# breakout1.net
KiCad netlist of a schematic drawn in EAGLE
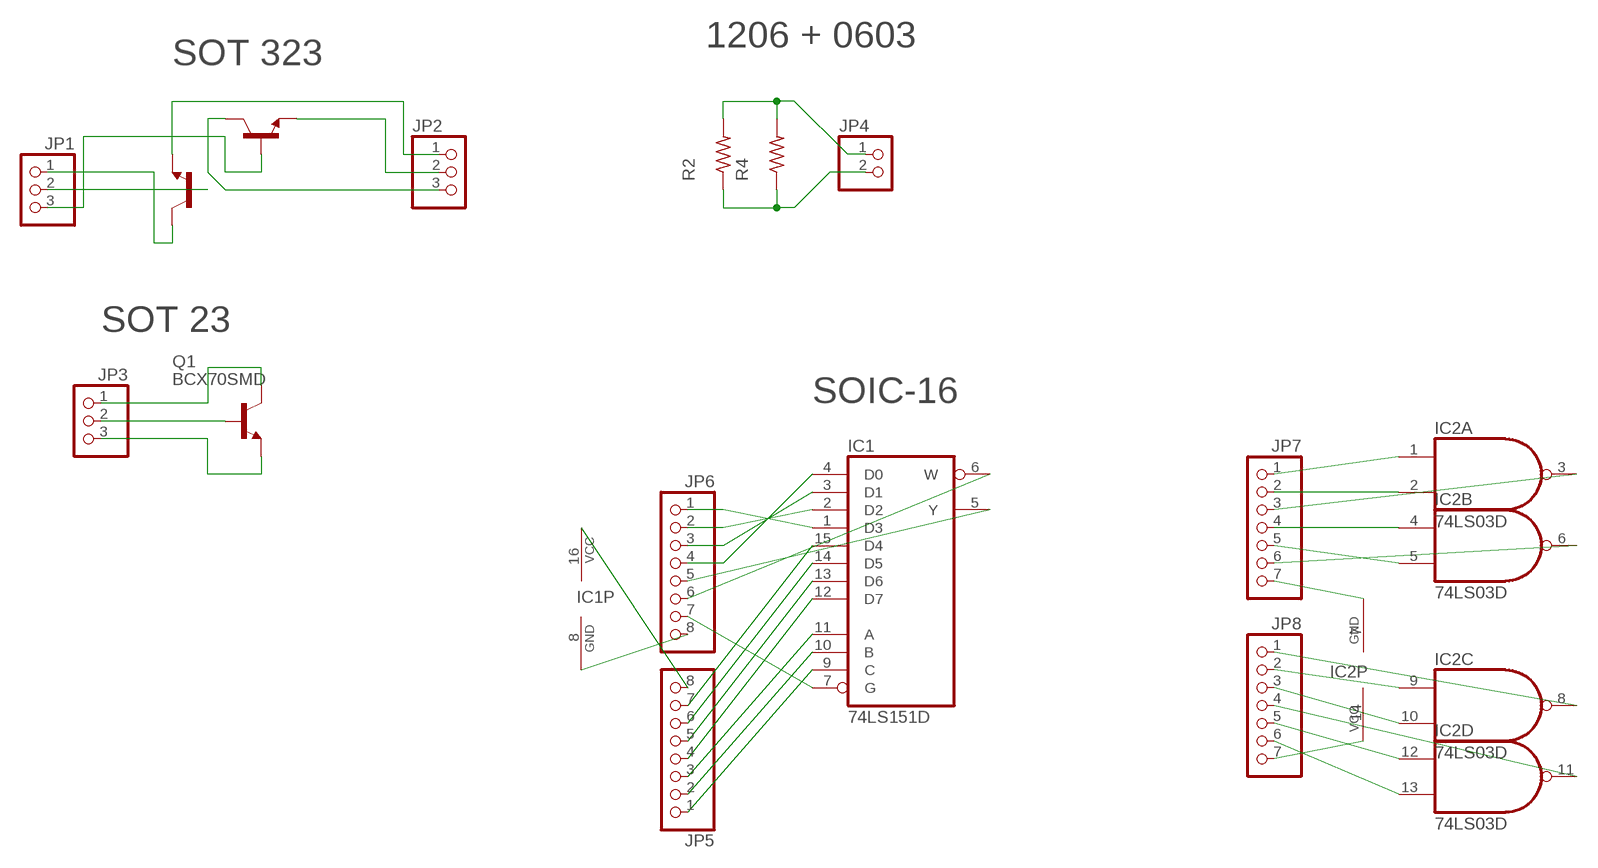
[diagram p0: schematic, sheet 1]

(export (version "E")
  (design (tool "Eeschema 10.0.6"))
  (components
    (comp (ref "IC1")
      (value "74LS151D")
      (footprint "eagle-import:SO16")
      (libsource (lib "eagle-import") (part "74151DLS"))
    )
    (comp (ref "IC2")
      (value "74LS03D")
      (footprint "eagle-import:SO14")
      (libsource (lib "eagle-import") (part "7403DLS"))
    )
    (comp (ref "JP1")
      (value "PINHD-1X3")
      (footprint "eagle-import:1X03")
      (libsource (lib "eagle-import") (part "PINHD-1X3"))
    )
    (comp (ref "JP2")
      (value "PINHD-1X3")
      (footprint "eagle-import:1X03")
      (libsource (lib "eagle-import") (part "PINHD-1X3"))
    )
    (comp (ref "JP3")
      (value "PINHD-1X3")
      (footprint "eagle-import:1X03")
      (libsource (lib "eagle-import") (part "PINHD-1X3"))
    )
    (comp (ref "JP4")
      (value "PINHD-1X2")
      (footprint "eagle-import:1X02")
      (libsource (lib "eagle-import") (part "PINHD-1X2"))
    )
    (comp (ref "JP5")
      (value "PINHD-1X8")
      (footprint "eagle-import:1X08")
      (libsource (lib "eagle-import") (part "PINHD-1X8"))
    )
    (comp (ref "JP6")
      (value "PINHD-1X8")
      (footprint "eagle-import:1X08")
      (libsource (lib "eagle-import") (part "PINHD-1X8"))
    )
    (comp (ref "JP7")
      (value "PINHD-1X7")
      (footprint "eagle-import:1X07")
      (libsource (lib "eagle-import") (part "PINHD-1X7"))
    )
    (comp (ref "JP8")
      (value "PINHD-1X7")
      (footprint "eagle-import:1X07")
      (libsource (lib "eagle-import") (part "PINHD-1X7"))
    )
    (comp (ref "Q1")
      (value "BCX70SMD")
      (footprint "eagle-import:SOT23")
      (libsource (lib "eagle-import") (part "BCX70SMD"))
    )
    (comp (ref "R2")
      (value "R-US_R0603")
      (footprint "eagle-import:R0603")
      (libsource (lib "eagle-import") (part "R-US_R0603"))
    )
    (comp (ref "R4")
      (value "R-US_R1206")
      (footprint "eagle-import:R1206")
      (libsource (lib "eagle-import") (part "R-US_R1206"))
    )
    (comp (ref "U$1")
      (value "DMMT3904W")
      (footprint "eagle-import:SOT363")
      (libsource (lib "eagle-import") (part "DMMT3904W"))
    )
  )
  (nets
    (net (code "1") (name "Net-(IC1A-A)") (class "Default")
      (node (ref "IC1") (pin "11") (pinfunction "A_11") (pintype "input"))
      (node (ref "JP5") (pin "3") (pinfunction "3_3") (pintype "passive"))
    )
    (net (code "2") (name "Net-(IC1A-B)") (class "Default")
      (node (ref "IC1") (pin "10") (pinfunction "B_10") (pintype "input"))
      (node (ref "JP5") (pin "2") (pinfunction "2_2") (pintype "passive"))
    )
    (net (code "3") (name "Net-(IC1A-C)") (class "Default")
      (node (ref "IC1") (pin "9") (pinfunction "C_9") (pintype "input"))
      (node (ref "JP5") (pin "1") (pinfunction "1_1") (pintype "passive"))
    )
    (net (code "4") (name "Net-(IC1A-D0)") (class "Default")
      (node (ref "IC1") (pin "4") (pinfunction "D0_4") (pintype "input"))
      (node (ref "JP6") (pin "4") (pinfunction "4_4") (pintype "passive"))
    )
    (net (code "5") (name "Net-(IC1A-D1)") (class "Default")
      (node (ref "IC1") (pin "3") (pinfunction "D1_3") (pintype "input"))
      (node (ref "JP6") (pin "3") (pinfunction "3_3") (pintype "passive"))
    )
    (net (code "6") (name "Net-(IC1A-D2)") (class "Default")
      (node (ref "IC1") (pin "2") (pinfunction "D2_2") (pintype "input"))
      (node (ref "JP6") (pin "2") (pinfunction "2_2") (pintype "passive"))
    )
    (net (code "7") (name "Net-(IC1A-D3)") (class "Default")
      (node (ref "IC1") (pin "1") (pinfunction "D3_1") (pintype "input"))
      (node (ref "JP6") (pin "1") (pinfunction "1_1") (pintype "passive"))
    )
    (net (code "8") (name "Net-(IC1A-D4)") (class "Default")
      (node (ref "IC1") (pin "15") (pinfunction "D4_15") (pintype "input"))
      (node (ref "JP5") (pin "7") (pinfunction "7_7") (pintype "passive"))
    )
    (net (code "9") (name "Net-(IC1A-D5)") (class "Default")
      (node (ref "IC1") (pin "14") (pinfunction "D5_14") (pintype "input"))
      (node (ref "JP5") (pin "6") (pinfunction "6_6") (pintype "passive"))
    )
    (net (code "10") (name "Net-(IC1A-D6)") (class "Default")
      (node (ref "IC1") (pin "13") (pinfunction "D6_13") (pintype "input"))
      (node (ref "JP5") (pin "5") (pinfunction "5_5") (pintype "passive"))
    )
    (net (code "11") (name "Net-(IC1A-D7)") (class "Default")
      (node (ref "IC1") (pin "12") (pinfunction "D7_12") (pintype "input"))
      (node (ref "JP5") (pin "4") (pinfunction "4_4") (pintype "passive"))
    )
    (net (code "12") (name "Net-(IC1A-G)") (class "Default")
      (node (ref "IC1") (pin "7") (pinfunction "G_7") (pintype "input"))
      (node (ref "JP6") (pin "7") (pinfunction "7_7") (pintype "passive"))
    )
    (net (code "13") (name "Net-(IC1A-W)") (class "Default")
      (node (ref "IC1") (pin "6") (pinfunction "W_6") (pintype "output"))
      (node (ref "JP6") (pin "6") (pinfunction "6_6") (pintype "passive"))
    )
    (net (code "14") (name "Net-(IC1A-Y)") (class "Default")
      (node (ref "IC1") (pin "5") (pinfunction "Y_5") (pintype "output"))
      (node (ref "JP6") (pin "5") (pinfunction "5_5") (pintype "passive"))
    )
    (net (code "15") (name "Net-(IC1B-GND)") (class "Default")
      (node (ref "IC1") (pin "8") (pinfunction "GND_8") (pintype "power_in"))
      (node (ref "JP6") (pin "8") (pinfunction "8_8") (pintype "passive"))
    )
    (net (code "16") (name "Net-(IC1B-VCC)") (class "Default")
      (node (ref "IC1") (pin "16") (pinfunction "VCC_16") (pintype "power_in"))
      (node (ref "JP5") (pin "8") (pinfunction "8_8") (pintype "passive"))
    )
    (net (code "17") (name "Net-(IC2A-I0)") (class "Default")
      (node (ref "IC2") (pin "1") (pinfunction "I0_1") (pintype "input"))
      (node (ref "JP7") (pin "1") (pinfunction "1_1") (pintype "passive"))
    )
    (net (code "18") (name "Net-(IC2A-I1)") (class "Default")
      (node (ref "IC2") (pin "2") (pinfunction "I1_2") (pintype "input"))
      (node (ref "JP7") (pin "2") (pinfunction "2_2") (pintype "passive"))
    )
    (net (code "19") (name "Net-(IC2A-O)") (class "Default")
      (node (ref "IC2") (pin "3") (pinfunction "O_3") (pintype "open_collector"))
      (node (ref "JP7") (pin "3") (pinfunction "3_3") (pintype "passive"))
    )
    (net (code "20") (name "Net-(IC2B-I0)") (class "Default")
      (node (ref "IC2") (pin "4") (pinfunction "I0_4") (pintype "input"))
      (node (ref "JP7") (pin "4") (pinfunction "4_4") (pintype "passive"))
    )
    (net (code "21") (name "Net-(IC2B-I1)") (class "Default")
      (node (ref "IC2") (pin "5") (pinfunction "I1_5") (pintype "input"))
      (node (ref "JP7") (pin "5") (pinfunction "5_5") (pintype "passive"))
    )
    (net (code "22") (name "Net-(IC2B-O)") (class "Default")
      (node (ref "IC2") (pin "6") (pinfunction "O_6") (pintype "open_collector"))
      (node (ref "JP7") (pin "6") (pinfunction "6_6") (pintype "passive"))
    )
    (net (code "23") (name "Net-(IC2C-I0)") (class "Default")
      (node (ref "IC2") (pin "9") (pinfunction "I0_9") (pintype "input"))
      (node (ref "JP8") (pin "2") (pinfunction "2_2") (pintype "passive"))
    )
    (net (code "24") (name "Net-(IC2C-I1)") (class "Default")
      (node (ref "IC2") (pin "10") (pinfunction "I1_10") (pintype "input"))
      (node (ref "JP8") (pin "3") (pinfunction "3_3") (pintype "passive"))
    )
    (net (code "25") (name "Net-(IC2C-O)") (class "Default")
      (node (ref "IC2") (pin "8") (pinfunction "O_8") (pintype "open_collector"))
      (node (ref "JP8") (pin "1") (pinfunction "1_1") (pintype "passive"))
    )
    (net (code "26") (name "Net-(IC2D-I0)") (class "Default")
      (node (ref "IC2") (pin "12") (pinfunction "I0_12") (pintype "input"))
      (node (ref "JP8") (pin "5") (pinfunction "5_5") (pintype "passive"))
    )
    (net (code "27") (name "Net-(IC2D-I1)") (class "Default")
      (node (ref "IC2") (pin "13") (pinfunction "I1_13") (pintype "input"))
      (node (ref "JP8") (pin "6") (pinfunction "6_6") (pintype "passive"))
    )
    (net (code "28") (name "Net-(IC2D-O)") (class "Default")
      (node (ref "IC2") (pin "11") (pinfunction "O_11") (pintype "open_collector"))
      (node (ref "JP8") (pin "4") (pinfunction "4_4") (pintype "passive"))
    )
    (net (code "29") (name "Net-(IC2E-GND)") (class "Default")
      (node (ref "IC2") (pin "7") (pinfunction "GND_7") (pintype "power_in"))
      (node (ref "JP7") (pin "7") (pinfunction "7_7") (pintype "passive"))
    )
    (net (code "30") (name "Net-(IC2E-VCC)") (class "Default")
      (node (ref "IC2") (pin "14") (pinfunction "VCC_14") (pintype "power_in"))
      (node (ref "JP8") (pin "7") (pinfunction "7_7") (pintype "passive"))
    )
    (net (code "31") (name "Net-(JP4-Pad1)") (class "Default")
      (node (ref "JP4") (pin "1") (pinfunction "1_1") (pintype "passive"))
      (node (ref "R2") (pin "2") (pinfunction "2_2") (pintype "passive"))
      (node (ref "R4") (pin "2") (pinfunction "2_2") (pintype "passive"))
    )
    (net (code "32") (name "Net-(JP4-Pad2)") (class "Default")
      (node (ref "JP4") (pin "2") (pinfunction "2_2") (pintype "passive"))
      (node (ref "R2") (pin "1") (pinfunction "1_1") (pintype "passive"))
      (node (ref "R4") (pin "1") (pinfunction "1_1") (pintype "passive"))
    )
    (net (code "33") (name "Net-(Q1-B)") (class "Default")
      (node (ref "JP3") (pin "2") (pinfunction "2_2") (pintype "passive"))
      (node (ref "Q1") (pin "1") (pinfunction "B_1") (pintype "passive"))
    )
    (net (code "34") (name "Net-(Q1-C)") (class "Default")
      (node (ref "JP3") (pin "1") (pinfunction "1_1") (pintype "passive"))
      (node (ref "Q1") (pin "3") (pinfunction "C_3") (pintype "passive"))
    )
    (net (code "35") (name "Net-(Q1-E)") (class "Default")
      (node (ref "JP3") (pin "3") (pinfunction "3_3") (pintype "passive"))
      (node (ref "Q1") (pin "2") (pinfunction "E_2") (pintype "passive"))
    )
    (net (code "36") (name "Net-(U$1A-B)") (class "Default")
      (node (ref "JP1") (pin "3") (pinfunction "3_3") (pintype "passive"))
      (node (ref "U$1") (pin "1") (pinfunction "B_1") (pintype "passive"))
    )
    (net (code "37") (name "Net-(U$1A-C)") (class "Default")
      (node (ref "JP2") (pin "3") (pinfunction "3_3") (pintype "passive"))
      (node (ref "U$1") (pin "6") (pinfunction "C_6") (pintype "passive"))
    )
    (net (code "38") (name "Net-(U$1A-E)") (class "Default")
      (node (ref "JP2") (pin "2") (pinfunction "2_2") (pintype "passive"))
      (node (ref "U$1") (pin "5") (pinfunction "E_5") (pintype "passive"))
    )
    (net (code "39") (name "Net-(U$1B-B)") (class "Default")
      (node (ref "JP1") (pin "2") (pinfunction "2_2") (pintype "passive"))
      (node (ref "U$1") (pin "2") (pinfunction "B_2") (pintype "passive"))
    )
    (net (code "40") (name "Net-(U$1B-C)") (class "Default")
      (node (ref "JP1") (pin "1") (pinfunction "1_1") (pintype "passive"))
      (node (ref "U$1") (pin "3") (pinfunction "C_3") (pintype "passive"))
    )
    (net (code "41") (name "Net-(U$1B-E)") (class "Default")
      (node (ref "JP2") (pin "1") (pinfunction "1_1") (pintype "passive"))
      (node (ref "U$1") (pin "4") (pinfunction "E_4") (pintype "passive"))
    )
  )
)
